# TIPIC_Schematic1.net
KiCad netlist of a schematic drawn in EAGLE
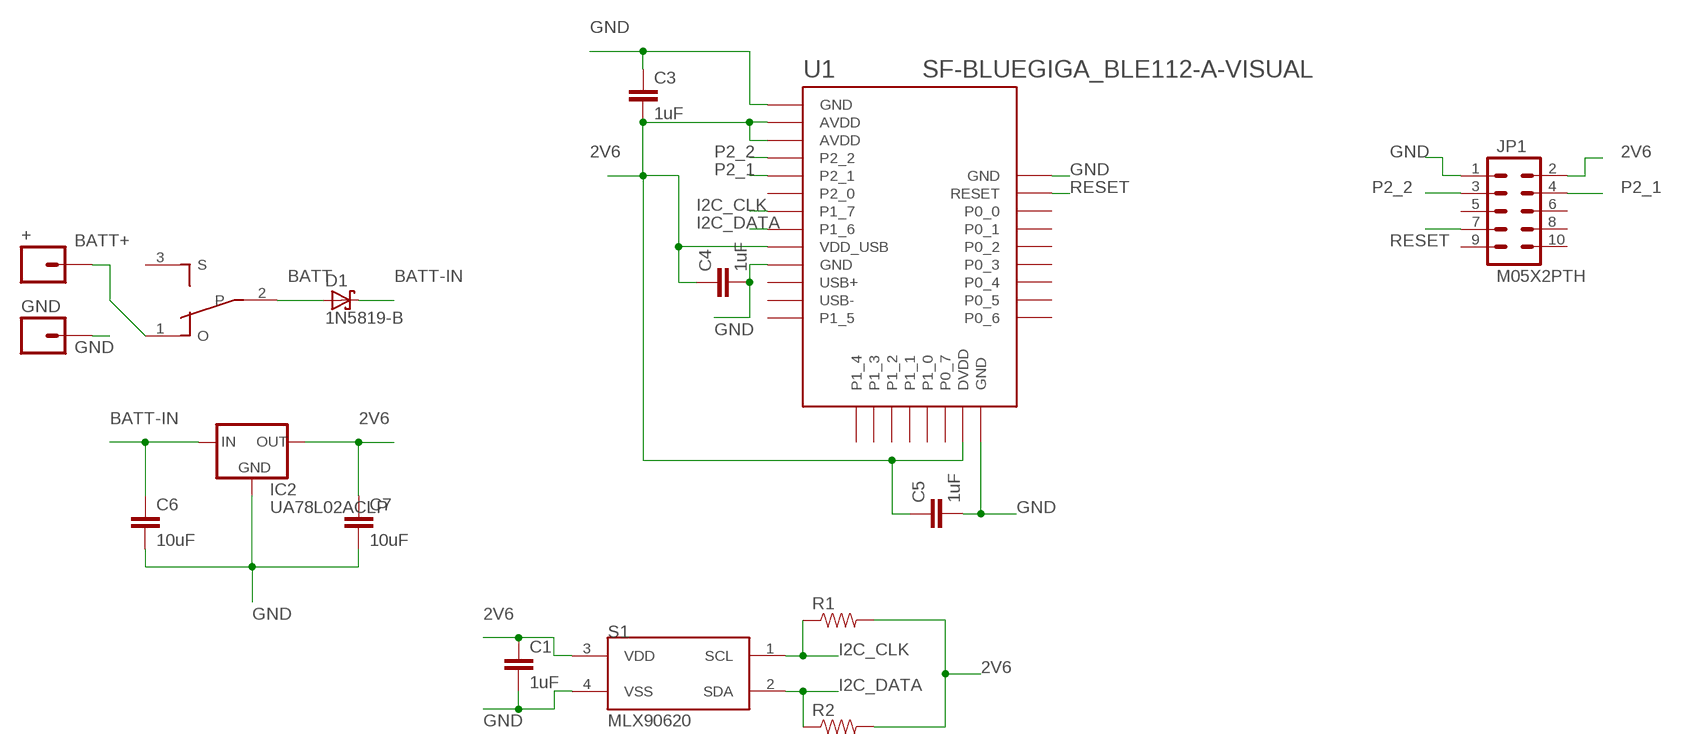
[diagram p0: schematic, sheet 1]

(export (version "E")
  (design (tool "Eeschema 10.0.6"))
  (components
    (comp (ref "+")
      (value "M01PTH")
      (footprint "eagle-import:1X01")
      (libsource (lib "eagle-import") (part "M01PTH"))
    )
    (comp (ref "C1")
      (value "1uF")
      (footprint "eagle-import:CAP-PTH-5MM")
      (libsource (lib "eagle-import") (part "CAPPTH1"))
    )
    (comp (ref "C3")
      (value "1uF")
      (footprint "eagle-import:CAP-PTH-5MM")
      (libsource (lib "eagle-import") (part "CAPPTH1"))
    )
    (comp (ref "C4")
      (value "1uF")
      (footprint "eagle-import:CAP-PTH-5MM")
      (libsource (lib "eagle-import") (part "CAPPTH1"))
    )
    (comp (ref "C5")
      (value "1uF")
      (footprint "eagle-import:CAP-PTH-5MM")
      (libsource (lib "eagle-import") (part "CAPPTH1"))
    )
    (comp (ref "C6")
      (value "10uF")
      (footprint "eagle-import:CAP-PTH-5MM")
      (libsource (lib "eagle-import") (part "CAPPTH1"))
    )
    (comp (ref "C7")
      (value "10uF")
      (footprint "eagle-import:CAP-PTH-5MM")
      (libsource (lib "eagle-import") (part "CAPPTH1"))
    )
    (comp (ref "D1")
      (value "1N5819-B")
      (footprint "eagle-import:DO41-7.6")
      (libsource (lib "eagle-import") (part "1N5819-B"))
    )
    (comp (ref "GND")
      (value "M01PTH")
      (footprint "eagle-import:1X01")
      (libsource (lib "eagle-import") (part "M01PTH"))
    )
    (comp (ref "IC2")
      (value "UA78L02ACLP")
      (footprint "eagle-import:TO-92")
      (libsource (lib "eagle-import") (part "2V6-VREG"))
    )
    (comp (ref "JP1")
      (value "M05X2PTH")
      (footprint "eagle-import:AVR_ICSP")
      (libsource (lib "eagle-import") (part "M05X2PTH"))
    )
    (comp (ref "R1")
      (value "RESISTORPTH-1/4W")
      (footprint "eagle-import:AXIAL-0.4")
      (libsource (lib "eagle-import") (part "RESISTORPTH-1/4W"))
    )
    (comp (ref "R2")
      (value "RESISTORPTH-1/4W")
      (footprint "eagle-import:AXIAL-0.4")
      (libsource (lib "eagle-import") (part "RESISTORPTH-1/4W"))
    )
    (comp (ref "S1")
      (value "MLX90620")
      (footprint "eagle-import:TO-39")
      (libsource (lib "eagle-import") (part "MLX90620"))
    )
    (comp (ref "S2")
      (value "SMALL_SWITCH")
      (footprint "eagle-import:EG1213")
      (libsource (lib "eagle-import") (part "SMALL_SWITCH"))
    )
    (comp (ref "U1")
      (value "SF-BLUEGIGA_BLE112-A-VISUAL")
      (footprint "eagle-import:SF-BLUEGIGA_BLE112-A")
      (libsource (lib "eagle-import") (part "SF-BLUEGIGA_BLE112-A-VISUAL"))
    )
  )
  (nets
    (net (code "1") (name "/2V6") (class "Default")
      (node (ref "C1") (pin "1") (pinfunction "1_1") (pintype "passive"))
      (node (ref "C3") (pin "2") (pinfunction "2_2") (pintype "passive"))
      (node (ref "C4") (pin "1") (pinfunction "1_1") (pintype "passive"))
      (node (ref "C5") (pin "1") (pinfunction "1_1") (pintype "passive"))
      (node (ref "C7") (pin "1") (pinfunction "1_1") (pintype "passive"))
      (node (ref "IC2") (pin "1") (pinfunction "OUT_1") (pintype "output"))
      (node (ref "JP1") (pin "2") (pinfunction "2_2") (pintype "passive"))
      (node (ref "R1") (pin "P$2") (pinfunction "2_P$2") (pintype "passive"))
      (node (ref "R2") (pin "P$2") (pinfunction "2_P$2") (pintype "passive"))
      (node (ref "S1") (pin "3") (pinfunction "VDD_3") (pintype "bidirectional"))
      (node (ref "U1") (pin "AVDD1") (pinfunction "AVDD_AVDD1") (pintype "power_in"))
      (node (ref "U1") (pin "AVDD2") (pinfunction "AVDD_AVDD2") (pintype "power_in"))
      (node (ref "U1") (pin "DVDD") (pinfunction "DVDD_DVDD") (pintype "power_in"))
      (node (ref "U1") (pin "VDD_USB") (pinfunction "VDD_USB_VDD_USB") (pintype "power_in"))
    )
    (net (code "2") (name "/BATT") (class "Default")
      (node (ref "D1") (pin "A") (pinfunction "A_A") (pintype "passive"))
      (node (ref "S2") (pin "2") (pinfunction "P_2") (pintype "bidirectional"))
    )
    (net (code "3") (name "/BATT+") (class "Default")
      (node (ref "+") (pin "1") (pinfunction "1_1") (pintype "passive"))
      (node (ref "S2") (pin "1") (pinfunction "O_1") (pintype "bidirectional"))
    )
    (net (code "4") (name "/BATT-IN") (class "Default")
      (node (ref "C6") (pin "1") (pinfunction "1_1") (pintype "passive"))
      (node (ref "D1") (pin "C") (pinfunction "C_C") (pintype "passive"))
      (node (ref "IC2") (pin "3") (pinfunction "IN_3") (pintype "input"))
    )
    (net (code "5") (name "/GND") (class "Default")
      (node (ref "C1") (pin "2") (pinfunction "2_2") (pintype "passive"))
      (node (ref "C3") (pin "1") (pinfunction "1_1") (pintype "passive"))
      (node (ref "C4") (pin "2") (pinfunction "2_2") (pintype "passive"))
      (node (ref "C5") (pin "2") (pinfunction "2_2") (pintype "passive"))
      (node (ref "C6") (pin "2") (pinfunction "2_2") (pintype "passive"))
      (node (ref "C7") (pin "2") (pinfunction "2_2") (pintype "passive"))
      (node (ref "GND") (pin "1") (pinfunction "1_1") (pintype "passive"))
      (node (ref "IC2") (pin "2") (pinfunction "GND_2") (pintype "input"))
      (node (ref "JP1") (pin "1") (pinfunction "1_1") (pintype "passive"))
      (node (ref "S1") (pin "4") (pinfunction "VSS_4") (pintype "bidirectional"))
      (node (ref "U1") (pin "GND1") (pinfunction "GND_GND1") (pintype "power_in"))
      (node (ref "U1") (pin "GND2") (pinfunction "GND_GND2") (pintype "power_in"))
      (node (ref "U1") (pin "GND3") (pinfunction "GND_GND3") (pintype "power_in"))
      (node (ref "U1") (pin "GND4") (pinfunction "GND_GND4") (pintype "power_in"))
    )
    (net (code "6") (name "/I2C_CLK") (class "Default")
      (node (ref "R1") (pin "P$1") (pinfunction "1_P$1") (pintype "passive"))
      (node (ref "S1") (pin "1") (pinfunction "SCL_1") (pintype "bidirectional"))
      (node (ref "U1") (pin "P1_7") (pinfunction "P1_7_P1_7") (pintype "bidirectional"))
    )
    (net (code "7") (name "/I2C_DATA") (class "Default")
      (node (ref "R2") (pin "P$1") (pinfunction "1_P$1") (pintype "passive"))
      (node (ref "S1") (pin "2") (pinfunction "SDA_2") (pintype "bidirectional"))
      (node (ref "U1") (pin "P1_6") (pinfunction "P1_6_P1_6") (pintype "bidirectional"))
    )
    (net (code "8") (name "/P2_1") (class "Default")
      (node (ref "JP1") (pin "4") (pinfunction "4_4") (pintype "passive"))
      (node (ref "U1") (pin "P2_1") (pinfunction "P2_1_P2_1") (pintype "bidirectional"))
    )
    (net (code "9") (name "/P2_2") (class "Default")
      (node (ref "JP1") (pin "3") (pinfunction "3_3") (pintype "passive"))
      (node (ref "U1") (pin "P2_2") (pinfunction "P2_2_P2_2") (pintype "bidirectional"))
    )
    (net (code "10") (name "/RESET") (class "Default")
      (node (ref "JP1") (pin "7") (pinfunction "7_7") (pintype "passive"))
      (node (ref "U1") (pin "RESET") (pinfunction "RESET_RESET") (pintype "input"))
    )
    (net (code "11") (name "unconnected-(JP1-Pad5)") (class "Default")
      (node (ref "JP1") (pin "5") (pinfunction "5_5") (pintype "passive"))
    )
    (net (code "12") (name "unconnected-(JP1-Pad6)") (class "Default")
      (node (ref "JP1") (pin "6") (pinfunction "6_6") (pintype "passive"))
    )
    (net (code "13") (name "unconnected-(JP1-Pad8)") (class "Default")
      (node (ref "JP1") (pin "8") (pinfunction "8_8") (pintype "passive"))
    )
    (net (code "14") (name "unconnected-(JP1-Pad9)") (class "Default")
      (node (ref "JP1") (pin "9") (pinfunction "9_9") (pintype "passive"))
    )
    (net (code "15") (name "unconnected-(JP1-Pad10)") (class "Default")
      (node (ref "JP1") (pin "10") (pinfunction "10_10") (pintype "passive"))
    )
    (net (code "16") (name "unconnected-(S2-S-Pad3)") (class "Default")
      (node (ref "S2") (pin "3") (pinfunction "S_3") (pintype "bidirectional"))
    )
    (net (code "17") (name "unconnected-(U1-PadP0_0)") (class "Default")
      (node (ref "U1") (pin "P0_0") (pinfunction "P0_0_P0_0") (pintype "bidirectional"))
    )
    (net (code "18") (name "unconnected-(U1-PadP0_1)") (class "Default")
      (node (ref "U1") (pin "P0_1") (pinfunction "P0_1_P0_1") (pintype "bidirectional"))
    )
    (net (code "19") (name "unconnected-(U1-PadP0_2)") (class "Default")
      (node (ref "U1") (pin "P0_2") (pinfunction "P0_2_P0_2") (pintype "bidirectional"))
    )
    (net (code "20") (name "unconnected-(U1-PadP0_3)") (class "Default")
      (node (ref "U1") (pin "P0_3") (pinfunction "P0_3_P0_3") (pintype "bidirectional"))
    )
    (net (code "21") (name "unconnected-(U1-PadP0_4)") (class "Default")
      (node (ref "U1") (pin "P0_4") (pinfunction "P0_4_P0_4") (pintype "bidirectional"))
    )
    (net (code "22") (name "unconnected-(U1-PadP0_5)") (class "Default")
      (node (ref "U1") (pin "P0_5") (pinfunction "P0_5_P0_5") (pintype "bidirectional"))
    )
    (net (code "23") (name "unconnected-(U1-PadP0_6)") (class "Default")
      (node (ref "U1") (pin "P0_6") (pinfunction "P0_6_P0_6") (pintype "bidirectional"))
    )
    (net (code "24") (name "unconnected-(U1-PadP0_7)") (class "Default")
      (node (ref "U1") (pin "P0_7") (pinfunction "P0_7_P0_7") (pintype "bidirectional"))
    )
    (net (code "25") (name "unconnected-(U1-PadP1_0)") (class "Default")
      (node (ref "U1") (pin "P1_0") (pinfunction "P1_0_P1_0") (pintype "bidirectional"))
    )
    (net (code "26") (name "unconnected-(U1-PadP1_1)") (class "Default")
      (node (ref "U1") (pin "P1_1") (pinfunction "P1_1_P1_1") (pintype "bidirectional"))
    )
    (net (code "27") (name "unconnected-(U1-PadP1_2)") (class "Default")
      (node (ref "U1") (pin "P1_2") (pinfunction "P1_2_P1_2") (pintype "bidirectional"))
    )
    (net (code "28") (name "unconnected-(U1-PadP1_3)") (class "Default")
      (node (ref "U1") (pin "P1_3") (pinfunction "P1_3_P1_3") (pintype "bidirectional"))
    )
    (net (code "29") (name "unconnected-(U1-PadP1_4)") (class "Default")
      (node (ref "U1") (pin "P1_4") (pinfunction "P1_4_P1_4") (pintype "bidirectional"))
    )
    (net (code "30") (name "unconnected-(U1-PadP1_5)") (class "Default")
      (node (ref "U1") (pin "P1_5") (pinfunction "P1_5_P1_5") (pintype "bidirectional"))
    )
    (net (code "31") (name "unconnected-(U1-PadP2_0)") (class "Default")
      (node (ref "U1") (pin "P2_0") (pinfunction "P2_0_P2_0") (pintype "bidirectional"))
    )
    (net (code "32") (name "unconnected-(U1-PadUSB+)") (class "Default")
      (node (ref "U1") (pin "USB+") (pinfunction "USB+_USB+") (pintype "bidirectional"))
    )
    (net (code "33") (name "unconnected-(U1-PadUSB-)") (class "Default")
      (node (ref "U1") (pin "USB-") (pinfunction "USB-_USB-") (pintype "bidirectional"))
    )
  )
)
